# temp.net
KiCad netlist of a schematic drawn in EAGLE
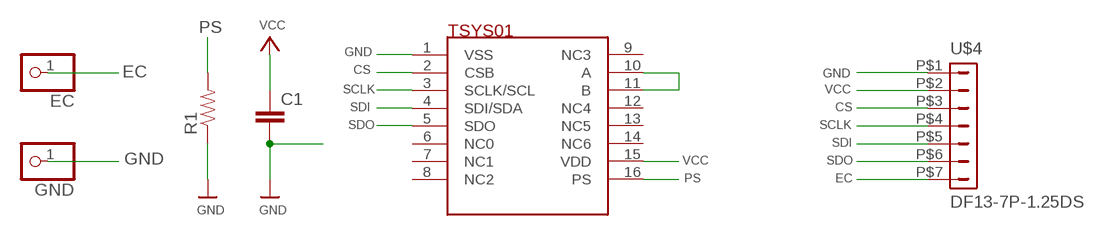
[diagram p0: schematic, sheet 1]

(export (version "E")
  (design (tool "Eeschema 10.0.6"))
  (components
    (comp (ref "C1")
      (value "CAP0402-CAP")
      (footprint "eagle-import:0402-CAP")
      (libsource (lib "eagle-import") (part "CAP0402-CAP"))
    )
    (comp (ref "EC")
      (value "PINHD-1X1")
      (footprint "eagle-import:1X01")
      (libsource (lib "eagle-import") (part "PINHD-1X1"))
    )
    (comp (ref "GND")
      (value "PINHD-1X1")
      (footprint "eagle-import:1X01")
      (libsource (lib "eagle-import") (part "PINHD-1X1"))
    )
    (comp (ref "R1")
      (value "RESISTOR0402-RES")
      (footprint "eagle-import:0402-RES")
      (libsource (lib "eagle-import") (part "RESISTOR0402-RES"))
    )
    (comp (ref "U$1")
      (value "TSYS01")
      (footprint "eagle-import:QFN16")
      (libsource (lib "eagle-import") (part "TSYS01"))
    )
    (comp (ref "U$4")
      (value "DF13-7P-1.25DS")
      (footprint "eagle-import:DF13-7P-1.25DS")
      (libsource (lib "eagle-import") (part "DF13-7P-1.25DS"))
    )
  )
  (nets
    (net (code "1") (name "/CS") (class "Default")
      (node (ref "U$1") (pin "2") (pinfunction "CSB_2") (pintype "bidirectional"))
      (node (ref "U$4") (pin "P$3") (pinfunction "3_P$3") (pintype "passive"))
    )
    (net (code "2") (name "/EC") (class "Default")
      (node (ref "EC") (pin "1") (pinfunction "1_1") (pintype "passive"))
      (node (ref "U$4") (pin "P$7") (pinfunction "7_P$7") (pintype "passive"))
    )
    (net (code "3") (name "/PS") (class "Default")
      (node (ref "R1") (pin "2") (pinfunction "2_2") (pintype "passive"))
      (node (ref "U$1") (pin "16") (pinfunction "PS_16") (pintype "bidirectional"))
    )
    (net (code "4") (name "/SCLK") (class "Default")
      (node (ref "U$1") (pin "3") (pinfunction "SCLK/SCL_3") (pintype "bidirectional"))
      (node (ref "U$4") (pin "P$4") (pinfunction "4_P$4") (pintype "passive"))
    )
    (net (code "5") (name "/SDI") (class "Default")
      (node (ref "U$1") (pin "4") (pinfunction "SDI/SDA_4") (pintype "bidirectional"))
      (node (ref "U$4") (pin "P$5") (pinfunction "5_P$5") (pintype "passive"))
    )
    (net (code "6") (name "/SDO") (class "Default")
      (node (ref "U$1") (pin "5") (pinfunction "SDO_5") (pintype "bidirectional"))
      (node (ref "U$4") (pin "P$6") (pinfunction "6_P$6") (pintype "passive"))
    )
    (net (code "7") (name "GND") (class "Default")
      (node (ref "C1") (pin "2") (pinfunction "2_2") (pintype "passive"))
      (node (ref "GND") (pin "1") (pinfunction "1_1") (pintype "passive"))
      (node (ref "R1") (pin "1") (pinfunction "1_1") (pintype "passive"))
      (node (ref "U$1") (pin "1") (pinfunction "VSS_1") (pintype "power_in"))
      (node (ref "U$4") (pin "P$1") (pinfunction "1_P$1") (pintype "passive"))
    )
    (net (code "8") (name "Net-(U$1-A)") (class "Default")
      (node (ref "U$1") (pin "10") (pinfunction "A_10") (pintype "bidirectional"))
      (node (ref "U$1") (pin "11") (pinfunction "B_11") (pintype "bidirectional"))
    )
    (net (code "9") (name "VCC") (class "Default")
      (node (ref "C1") (pin "1") (pinfunction "1_1") (pintype "passive"))
      (node (ref "U$1") (pin "15") (pinfunction "VDD_15") (pintype "power_in"))
      (node (ref "U$4") (pin "P$2") (pinfunction "2_P$2") (pintype "passive"))
    )
    (net (code "10") (name "unconnected-(U$1-NC0-Pad6)") (class "Default")
      (node (ref "U$1") (pin "6") (pinfunction "NC0_6") (pintype "no_connect"))
    )
    (net (code "11") (name "unconnected-(U$1-NC1-Pad7)") (class "Default")
      (node (ref "U$1") (pin "7") (pinfunction "NC1_7") (pintype "no_connect"))
    )
    (net (code "12") (name "unconnected-(U$1-NC2-Pad8)") (class "Default")
      (node (ref "U$1") (pin "8") (pinfunction "NC2_8") (pintype "no_connect"))
    )
    (net (code "13") (name "unconnected-(U$1-NC3-Pad9)") (class "Default")
      (node (ref "U$1") (pin "9") (pinfunction "NC3_9") (pintype "no_connect"))
    )
    (net (code "14") (name "unconnected-(U$1-NC4-Pad12)") (class "Default")
      (node (ref "U$1") (pin "12") (pinfunction "NC4_12") (pintype "no_connect"))
    )
    (net (code "15") (name "unconnected-(U$1-NC5-Pad13)") (class "Default")
      (node (ref "U$1") (pin "13") (pinfunction "NC5_13") (pintype "no_connect"))
    )
    (net (code "16") (name "unconnected-(U$1-NC6-Pad14)") (class "Default")
      (node (ref "U$1") (pin "14") (pinfunction "NC6_14") (pintype "no_connect"))
    )
  )
)
